# led.net
KiCad netlist of a schematic drawn in Altium Designer
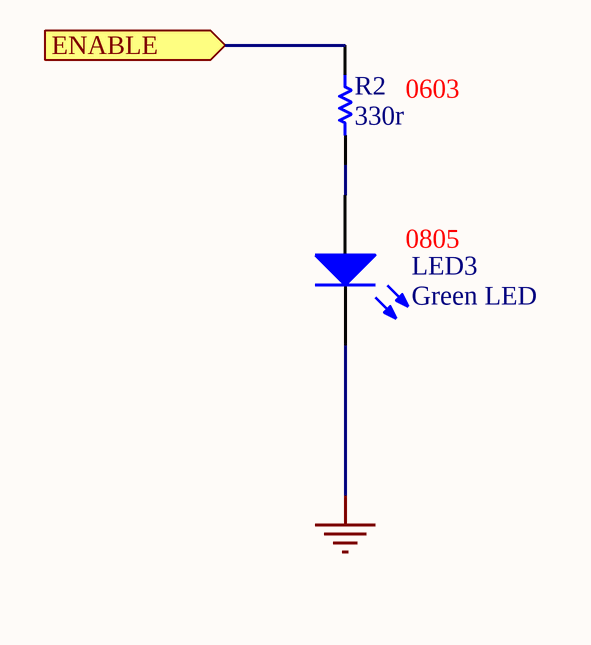
[diagram p0: led.SchDoc]

(export (version "E")
  (design (tool "Eeschema 10.0.6"))
  (components
    (comp (ref "LED3")
      (value "Green LED")
      (footprint "0805")
      (description "Typical RED, GREEN, YELLOW, AMBER GaAs LED")
      (fields (field (name "PUBLISHER") "Altium Limited"))
      (libsource (lib "Miscellaneous Devices") (part "LED2"))
    )
    (comp (ref "R2")
      (value "330r")
      (footprint "0603")
      (description "Resistor")
      (fields (field (name "PUBLISHER") "Altium Limited"))
      (libsource (lib "Miscellaneous Devices") (part "Res1"))
    )
  )
  (nets
    (net (code "1") (name "/ENABLE") (class "Default")
      (node (ref "R2") (pin "1") (pinfunction "1_1") (pintype "passive"))
    )
    (net (code "2") (name "GND") (class "Default")
      (node (ref "LED3") (pin "2") (pinfunction "K_2") (pintype "passive"))
    )
    (net (code "3") (name "Net-(LED3-A)") (class "Default")
      (node (ref "LED3") (pin "1") (pinfunction "A_1") (pintype "passive"))
      (node (ref "R2") (pin "2") (pinfunction "2_2") (pintype "passive"))
    )
  )
)
